# ha-pc-switch-revA.net
KiCad netlist of a schematic drawn in EAGLE
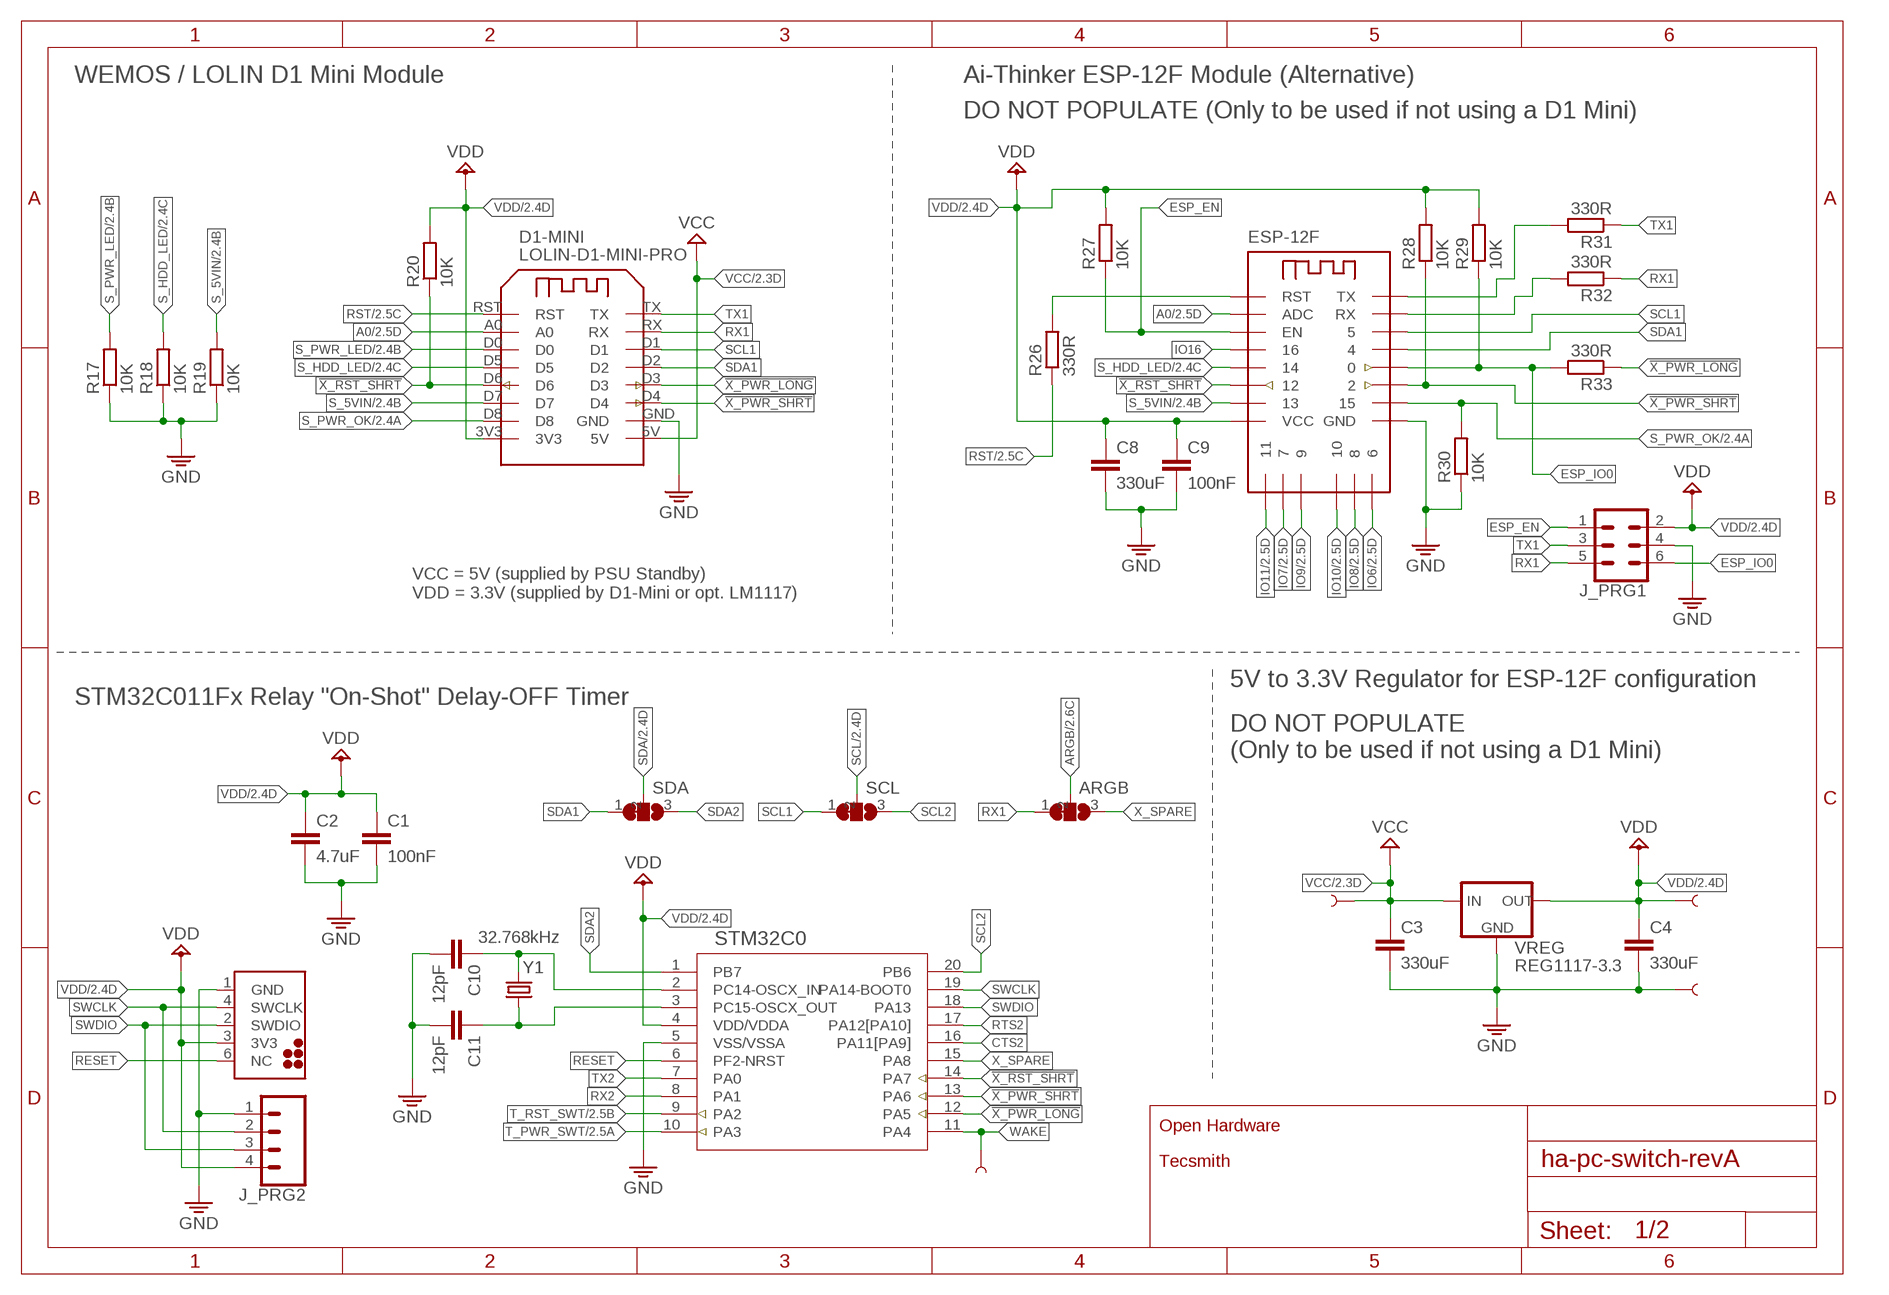
[diagram p0: schematic, sheet 1]
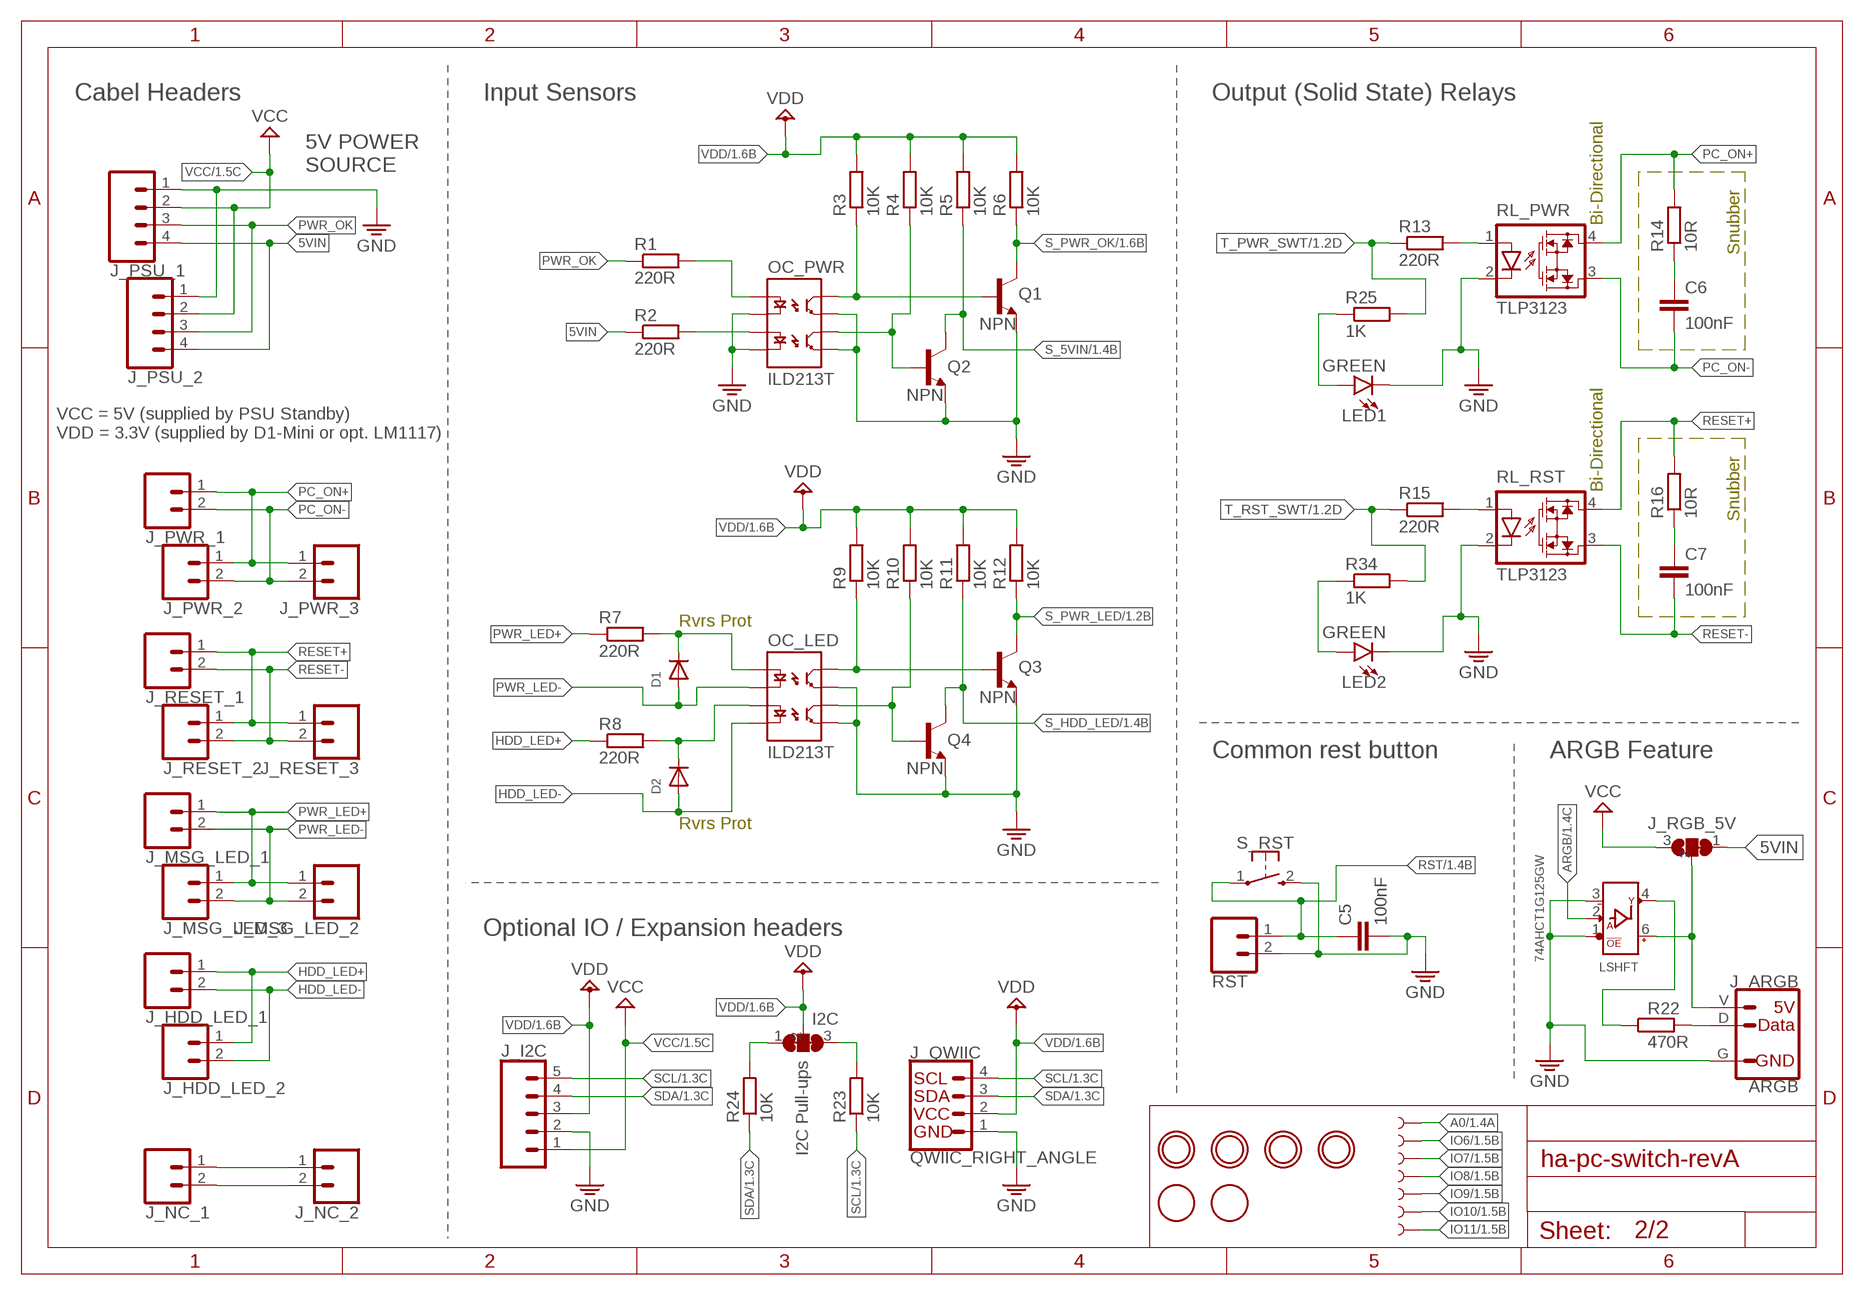
[diagram p1: schematic, sheet 2]

(export (version "E")
  (design (tool "Eeschema 10.0.6"))
  (components
    (comp (ref "ARGB")
      (value "JUMPER-1X3-CLOSED")
      (footprint "eagle-import:SOLDERJUMPER_CLOSEDWIRE-3")
      (libsource (lib "eagle-import") (part "JUMPER-1X3-CLOSED"))
    )
    (comp (ref "C1")
      (value "100nF")
      (footprint "eagle-import:C0603")
      (libsource (lib "eagle-import") (part "C-EUC0603"))
    )
    (comp (ref "C2")
      (value "4.7uF")
      (footprint "eagle-import:C0603")
      (libsource (lib "eagle-import") (part "C-EUC0603"))
    )
    (comp (ref "C3")
      (value "330uF")
      (footprint "eagle-import:C0603")
      (libsource (lib "eagle-import") (part "C-EUC0603"))
    )
    (comp (ref "C4")
      (value "330uF")
      (footprint "eagle-import:C0603")
      (libsource (lib "eagle-import") (part "C-EUC0603"))
    )
    (comp (ref "C8")
      (value "330uF")
      (footprint "eagle-import:C0603")
      (libsource (lib "eagle-import") (part "C-EUC0603"))
    )
    (comp (ref "C9")
      (value "100nF")
      (footprint "eagle-import:C0603")
      (libsource (lib "eagle-import") (part "C-EUC0603"))
    )
    (comp (ref "C10")
      (value "12pF")
      (footprint "eagle-import:C0603")
      (libsource (lib "eagle-import") (part "C-EUC0603"))
    )
    (comp (ref "C11")
      (value "12pF")
      (footprint "eagle-import:C0603")
      (libsource (lib "eagle-import") (part "C-EUC0603"))
    )
    (comp (ref "D1-MINI")
      (value "LOLIN-D1-MINI-PRO")
      (footprint "eagle-import:WEMOS-D1-MINI-PRO")
      (libsource (lib "eagle-import") (part "LOLIN-D1-MINI-PRO"))
    )
    (comp (ref "ESP-12F")
      (value "ESPRESSIF-ESP-12F&ESMD")
      (footprint "eagle-import:ESP8266-ESP-12E")
      (libsource (lib "eagle-import") (part "ESPRESSIF-ESP-12F&ESMD"))
    )
    (comp (ref "J_DBG2")
      (value "NUCLEO_HEADER")
      (footprint "eagle-import:NUCLEO")
      (libsource (lib "eagle-import") (part "NUCLEO_HEADER"))
    )
    (comp (ref "J_PRG1")
      (value "CONN_03X2FEMALE_SMD")
      (footprint "eagle-import:2X3_SMD")
      (libsource (lib "eagle-import") (part "CONN_03X2FEMALE_SMD"))
    )
    (comp (ref "J_PRG2")
      (value "1X04_SMD_STRAIGHT_COMBO")
      (footprint "eagle-import:1X04_SMD_VERTICAL_COMBO")
      (libsource (lib "eagle-import") (part "CONN_04SMD_STRAIGHT_COMBO"))
    )
    (comp (ref "LOGO1")
      (value "OSHW-LOGOM")
      (footprint "eagle-import:OSHW-LOGO-M")
      (libsource (lib "eagle-import") (part "OSHW-LOGOM"))
    )
    (comp (ref "R17")
      (value "10K")
      (footprint "eagle-import:R0603")
      (libsource (lib "eagle-import") (part "R-EU_R0603"))
    )
    (comp (ref "R18")
      (value "10K")
      (footprint "eagle-import:R0603")
      (libsource (lib "eagle-import") (part "R-EU_R0603"))
    )
    (comp (ref "R19")
      (value "10K")
      (footprint "eagle-import:R0603")
      (libsource (lib "eagle-import") (part "R-EU_R0603"))
    )
    (comp (ref "R20")
      (value "10K")
      (footprint "eagle-import:R0603")
      (libsource (lib "eagle-import") (part "R-EU_R0603"))
    )
    (comp (ref "R26")
      (value "330R")
      (footprint "eagle-import:R0603")
      (libsource (lib "eagle-import") (part "R-EU_R0603"))
    )
    (comp (ref "R27")
      (value "10K")
      (footprint "eagle-import:R0603")
      (libsource (lib "eagle-import") (part "R-EU_R0603"))
    )
    (comp (ref "R28")
      (value "10K")
      (footprint "eagle-import:R0603")
      (libsource (lib "eagle-import") (part "R-EU_R0603"))
    )
    (comp (ref "R29")
      (value "10K")
      (footprint "eagle-import:R0603")
      (libsource (lib "eagle-import") (part "R-EU_R0603"))
    )
    (comp (ref "R30")
      (value "10K")
      (footprint "eagle-import:R0603")
      (libsource (lib "eagle-import") (part "R-EU_R0603"))
    )
    (comp (ref "R31")
      (value "330R")
      (footprint "eagle-import:R0603")
      (libsource (lib "eagle-import") (part "R-EU_R0603"))
    )
    (comp (ref "R32")
      (value "330R")
      (footprint "eagle-import:R0603")
      (libsource (lib "eagle-import") (part "R-EU_R0603"))
    )
    (comp (ref "R33")
      (value "330R")
      (footprint "eagle-import:R0603")
      (libsource (lib "eagle-import") (part "R-EU_R0603"))
    )
    (comp (ref "SCL")
      (value "JUMPER-1X3-CLOSED")
      (footprint "eagle-import:SOLDERJUMPER_CLOSEDWIRE-3")
      (libsource (lib "eagle-import") (part "JUMPER-1X3-CLOSED"))
    )
    (comp (ref "SDA")
      (value "JUMPER-1X3-CLOSED")
      (footprint "eagle-import:SOLDERJUMPER_CLOSEDWIRE-3")
      (libsource (lib "eagle-import") (part "JUMPER-1X3-CLOSED"))
    )
    (comp (ref "STM32C0")
      (value "STM32C011FTSSOP20_STM-M")
      (footprint "eagle-import:TSSOP20-M")
      (fields
        (field (name "MANUFACTURER_PART_NUMBER") "STM32C011F4P6")
        (field (name "COPYRIGHT") "Copyright (C) 2024 Ultra Librarian. All rights reserved.")
      )
      (libsource (lib "eagle-import") (part "STM32C011FTSSOP20_STM-M"))
    )
    (comp (ref "TP1")
      (value "TEST-POINT3X5")
      (footprint "eagle-import:PAD.03X.05")
      (libsource (lib "eagle-import") (part "TEST-POINT3X5"))
    )
    (comp (ref "TP2")
      (value "TEST-POINT3X5")
      (footprint "eagle-import:PAD.03X.05")
      (libsource (lib "eagle-import") (part "TEST-POINT3X5"))
    )
    (comp (ref "TP3")
      (value "TEST-POINT3X5")
      (footprint "eagle-import:PAD.03X.05")
      (libsource (lib "eagle-import") (part "TEST-POINT3X5"))
    )
    (comp (ref "TP4")
      (value "TEST-POINT3X5")
      (footprint "eagle-import:PAD.03X.05")
      (libsource (lib "eagle-import") (part "TEST-POINT3X5"))
    )
    (comp (ref "U$1")
      (value "TECSMITH-LOGOLONG")
      (footprint "eagle-import:TECSMITH-NAME")
      (libsource (lib "eagle-import") (part "TECSMITH-LOGOLONG"))
    )
    (comp (ref "VREG")
      (value "REG1117-3.3")
      (footprint "eagle-import:SOT223")
      (libsource (lib "eagle-import") (part "REG1117-3.3"))
    )
    (comp (ref "Y1")
      (value "32.768kHz")
      (footprint "eagle-import:CRYSTAL-SMD-3.2X1.5MM")
      (libsource (lib "eagle-import") (part "CRYSTAL-32.768KHZSMD-3.2X1.5"))
    )
    (comp (ref "C5")
      (value "100nF")
      (footprint "eagle-import:C0603")
      (libsource (lib "eagle-import") (part "C-EUC0603"))
    )
    (comp (ref "C6")
      (value "100nF")
      (footprint "eagle-import:C0603")
      (libsource (lib "eagle-import") (part "C-EUC0603"))
    )
    (comp (ref "C7")
      (value "100nF")
      (footprint "eagle-import:C0603")
      (libsource (lib "eagle-import") (part "C-EUC0603"))
    )
    (comp (ref "D1")
      (value "DIODESOD-523")
      (footprint "eagle-import:SOD-523")
      (libsource (lib "eagle-import") (part "DIODESOD-523"))
    )
    (comp (ref "D2")
      (value "DIODESOD-523")
      (footprint "eagle-import:SOD-523")
      (libsource (lib "eagle-import") (part "DIODESOD-523"))
    )
    (comp (ref "I2C")
      (value "JUMPER-1X3-CLOSED-2")
      (footprint "eagle-import:SOLDERJUMPER_CLOSEDWIRE-3-2")
      (libsource (lib "eagle-import") (part "JUMPER-1X3-CLOSED-2"))
    )
    (comp (ref "J_ARGB")
      (value "ARGB")
      (footprint "eagle-import:ARGB")
      (libsource (lib "eagle-import") (part "ARGB"))
    )
    (comp (ref "J_HDD_LED_1")
      (value "CONN_021X02_NO_SILK")
      (footprint "eagle-import:1X02_NO_SILK")
      (libsource (lib "eagle-import") (part "CONN_021X02_NO_SILK"))
    )
    (comp (ref "J_HDD_LED_2")
      (value "CONN_021X02_NO_SILK")
      (footprint "eagle-import:1X02_NO_SILK")
      (libsource (lib "eagle-import") (part "CONN_021X02_NO_SILK"))
    )
    (comp (ref "J_I2C")
      (value "CONN_05SCREW")
      (footprint "eagle-import:SCREWTERMINAL-3.5MM-5")
      (libsource (lib "eagle-import") (part "CONN_05SCREW"))
    )
    (comp (ref "J_MSG_LED_1")
      (value "CONN_021X02_NO_SILK")
      (footprint "eagle-import:1X02_NO_SILK")
      (libsource (lib "eagle-import") (part "CONN_021X02_NO_SILK"))
    )
    (comp (ref "J_MSG_LED_2")
      (value "CONN_021X02_NO_SILK")
      (footprint "eagle-import:1X02_NO_SILK")
      (libsource (lib "eagle-import") (part "CONN_021X02_NO_SILK"))
    )
    (comp (ref "J_MSG_LED_3")
      (value "CONN_02PTH3")
      (footprint "eagle-import:1X02_LONGPADS")
      (libsource (lib "eagle-import") (part "CONN_02PTH3"))
    )
    (comp (ref "J_NC_1")
      (value "CONN_021X02_NO_SILK")
      (footprint "eagle-import:1X02_NO_SILK")
      (libsource (lib "eagle-import") (part "CONN_021X02_NO_SILK"))
    )
    (comp (ref "J_NC_2")
      (value "CONN_021X02_NO_SILK")
      (footprint "eagle-import:1X02_NO_SILK")
      (libsource (lib "eagle-import") (part "CONN_021X02_NO_SILK"))
    )
    (comp (ref "J_PSU_1")
      (value "CONN_04LONGPADS")
      (footprint "eagle-import:1X04_LONGPADS")
      (libsource (lib "eagle-import") (part "CONN_04LONGPADS"))
    )
    (comp (ref "J_PSU_2")
      (value "CONN_04SCREW")
      (footprint "eagle-import:SCREWTERMINAL-3.5MM-4")
      (libsource (lib "eagle-import") (part "CONN_04SCREW"))
    )
    (comp (ref "J_PWR_1")
      (value "CONN_021X02_NO_SILK")
      (footprint "eagle-import:1X02_NO_SILK")
      (libsource (lib "eagle-import") (part "CONN_021X02_NO_SILK"))
    )
    (comp (ref "J_PWR_2")
      (value "CONN_021X02_NO_SILK")
      (footprint "eagle-import:1X02_NO_SILK")
      (libsource (lib "eagle-import") (part "CONN_021X02_NO_SILK"))
    )
    (comp (ref "J_PWR_3")
      (value "CONN_02PTH3")
      (footprint "eagle-import:1X02_LONGPADS")
      (libsource (lib "eagle-import") (part "CONN_02PTH3"))
    )
    (comp (ref "J_QWIIC")
      (value "QWIIC_RIGHT_ANGLE")
      (footprint "eagle-import:JST04_1MM_RA")
      (libsource (lib "eagle-import") (part "QWIIC_CONNECTORJS-1MM"))
    )
    (comp (ref "J_RESET_1")
      (value "CONN_021X02_NO_SILK")
      (footprint "eagle-import:1X02_NO_SILK")
      (libsource (lib "eagle-import") (part "CONN_021X02_NO_SILK"))
    )
    (comp (ref "J_RESET_2")
      (value "CONN_021X02_NO_SILK")
      (footprint "eagle-import:1X02_NO_SILK")
      (libsource (lib "eagle-import") (part "CONN_021X02_NO_SILK"))
    )
    (comp (ref "J_RESET_3")
      (value "CONN_02PTH3")
      (footprint "eagle-import:1X02_LONGPADS")
      (libsource (lib "eagle-import") (part "CONN_02PTH3"))
    )
    (comp (ref "J_RGB_5V")
      (value "JUMPER-1X3-CLOSEDPINS")
      (footprint "eagle-import:1X03_ROUND_CLOSED")
      (libsource (lib "eagle-import") (part "JUMPER-1X3-CLOSEDPINS"))
    )
    (comp (ref "LED1")
      (value "GREEN")
      (footprint "eagle-import:LED-0603")
      (libsource (lib "eagle-import") (part "LED-GREEN0603"))
    )
    (comp (ref "LED2")
      (value "GREEN")
      (footprint "eagle-import:LED-0603")
      (libsource (lib "eagle-import") (part "LED-GREEN0603"))
    )
    (comp (ref "LSHFT")
      (value "74AHCT1G125GW")
      (footprint "eagle-import:SC-88A__TSSOP5__SOT353-1")
      (libsource (lib "eagle-import") (part "74AHCT1G125GW"))
    )
    (comp (ref "OC_LED")
      (value "ILD213T")
      (footprint "eagle-import:SO08-2")
      (libsource (lib "eagle-import") (part "OPTOISOLATOR-2SOIC8"))
    )
    (comp (ref "OC_PWR")
      (value "ILD213T")
      (footprint "eagle-import:SO08-2")
      (libsource (lib "eagle-import") (part "OPTOISOLATOR-2SOIC8"))
    )
    (comp (ref "Q1")
      (value "NPN")
      (footprint "eagle-import:SOT23-3")
      (libsource (lib "eagle-import") (part "TRANSISTOR_NPNSOT23-3"))
    )
    (comp (ref "Q2")
      (value "NPN")
      (footprint "eagle-import:SOT23-3")
      (libsource (lib "eagle-import") (part "TRANSISTOR_NPNSOT23-3"))
    )
    (comp (ref "Q3")
      (value "NPN")
      (footprint "eagle-import:SOT23-3")
      (libsource (lib "eagle-import") (part "TRANSISTOR_NPNSOT23-3"))
    )
    (comp (ref "Q4")
      (value "NPN")
      (footprint "eagle-import:SOT23-3")
      (libsource (lib "eagle-import") (part "TRANSISTOR_NPNSOT23-3"))
    )
    (comp (ref "R1")
      (value "220R")
      (footprint "eagle-import:R0603")
      (libsource (lib "eagle-import") (part "R-EU_R0603"))
    )
    (comp (ref "R2")
      (value "220R")
      (footprint "eagle-import:R0603")
      (libsource (lib "eagle-import") (part "R-EU_R0603"))
    )
    (comp (ref "R3")
      (value "10K")
      (footprint "eagle-import:R0603")
      (libsource (lib "eagle-import") (part "R-EU_R0603"))
    )
    (comp (ref "R4")
      (value "10K")
      (footprint "eagle-import:R0603")
      (libsource (lib "eagle-import") (part "R-EU_R0603"))
    )
    (comp (ref "R5")
      (value "10K")
      (footprint "eagle-import:R0603")
      (libsource (lib "eagle-import") (part "R-EU_R0603"))
    )
    (comp (ref "R6")
      (value "10K")
      (footprint "eagle-import:R0603")
      (libsource (lib "eagle-import") (part "R-EU_R0603"))
    )
    (comp (ref "R7")
      (value "220R")
      (footprint "eagle-import:R0603")
      (libsource (lib "eagle-import") (part "R-EU_R0603"))
    )
    (comp (ref "R8")
      (value "220R")
      (footprint "eagle-import:R0603")
      (libsource (lib "eagle-import") (part "R-EU_R0603"))
    )
    (comp (ref "R9")
      (value "10K")
      (footprint "eagle-import:R0603")
      (libsource (lib "eagle-import") (part "R-EU_R0603"))
    )
    (comp (ref "R10")
      (value "10K")
      (footprint "eagle-import:R0603")
      (libsource (lib "eagle-import") (part "R-EU_R0603"))
    )
    (comp (ref "R11")
      (value "10K")
      (footprint "eagle-import:R0603")
      (libsource (lib "eagle-import") (part "R-EU_R0603"))
    )
    (comp (ref "R12")
      (value "10K")
      (footprint "eagle-import:R0603")
      (libsource (lib "eagle-import") (part "R-EU_R0603"))
    )
    (comp (ref "R13")
      (value "220R")
      (footprint "eagle-import:R0603")
      (libsource (lib "eagle-import") (part "R-EU_R0603"))
    )
    (comp (ref "R14")
      (value "10R")
      (footprint "eagle-import:R0603")
      (libsource (lib "eagle-import") (part "R-EU_R0603"))
    )
    (comp (ref "R15")
      (value "220R")
      (footprint "eagle-import:R0603")
      (libsource (lib "eagle-import") (part "R-EU_R0603"))
    )
    (comp (ref "R16")
      (value "10R")
      (footprint "eagle-import:R0603")
      (libsource (lib "eagle-import") (part "R-EU_R0603"))
    )
    (comp (ref "R22")
      (value "470R")
      (footprint "eagle-import:R0603")
      (libsource (lib "eagle-import") (part "R-EU_R0603"))
    )
    (comp (ref "R23")
      (value "10K")
      (footprint "eagle-import:R0603")
      (libsource (lib "eagle-import") (part "R-EU_R0603"))
    )
    (comp (ref "R24")
      (value "10K")
      (footprint "eagle-import:R0603")
      (libsource (lib "eagle-import") (part "R-EU_R0603"))
    )
    (comp (ref "R25")
      (value "1K")
      (footprint "eagle-import:R0603")
      (libsource (lib "eagle-import") (part "R-EU_R0603"))
    )
    (comp (ref "R34")
      (value "1K")
      (footprint "eagle-import:R0603")
      (libsource (lib "eagle-import") (part "R-EU_R0603"))
    )
    (comp (ref "RL_PWR")
      (value "TLP3123")
      (footprint "eagle-import:SOP4_TOS")
      (libsource (lib "eagle-import") (part "TLP3123"))
    )
    (comp (ref "RL_RST")
      (value "TLP3123")
      (footprint "eagle-import:SOP4_TOS")
      (libsource (lib "eagle-import") (part "TLP3123"))
    )
    (comp (ref "RST")
      (value "CONN_021X02_NO_SILK")
      (footprint "eagle-import:1X02_NO_SILK")
      (libsource (lib "eagle-import") (part "CONN_021X02_NO_SILK"))
    )
    (comp (ref "S_RST")
      (value "MOMENTARY-SWITCH-SPST-1")
      (footprint "eagle-import:SKRKAEE020")
      (libsource (lib "eagle-import") (part "MOMENTARY-SWITCH-SPST-1"))
    )
    (comp (ref "TP9")
      (value "TEST-POINT3X5")
      (footprint "eagle-import:PAD.03X.05")
      (libsource (lib "eagle-import") (part "TEST-POINT3X5"))
    )
    (comp (ref "TP10")
      (value "TEST-POINT3X5")
      (footprint "eagle-import:PAD.03X.05")
      (libsource (lib "eagle-import") (part "TEST-POINT3X5"))
    )
    (comp (ref "TP11")
      (value "TEST-POINT3X5")
      (footprint "eagle-import:PAD.03X.05")
      (libsource (lib "eagle-import") (part "TEST-POINT3X5"))
    )
    (comp (ref "TP12")
      (value "TEST-POINT3X5")
      (footprint "eagle-import:PAD.03X.05")
      (libsource (lib "eagle-import") (part "TEST-POINT3X5"))
    )
    (comp (ref "TP14")
      (value "TEST-POINT3X5")
      (footprint "eagle-import:PAD.03X.05")
      (libsource (lib "eagle-import") (part "TEST-POINT3X5"))
    )
    (comp (ref "TP15")
      (value "TEST-POINT3X5")
      (footprint "eagle-import:PAD.03X.05")
      (libsource (lib "eagle-import") (part "TEST-POINT3X5"))
    )
    (comp (ref "TP16")
      (value "TEST-POINT3X5")
      (footprint "eagle-import:PAD.03X.05")
      (libsource (lib "eagle-import") (part "TEST-POINT3X5"))
    )
    (comp (ref "U$5")
      (value "MOUNTINGHOLE3.0THIN")
      (footprint "eagle-import:MOUNTINGHOLE_3.0_PLATEDTHIN")
      (libsource (lib "eagle-import") (part "MOUNTINGHOLE3.0THIN"))
    )
    (comp (ref "U$9")
      (value "MOUNTINGHOLE3.0THIN")
      (footprint "eagle-import:MOUNTINGHOLE_3.0_PLATEDTHIN")
      (libsource (lib "eagle-import") (part "MOUNTINGHOLE3.0THIN"))
    )
    (comp (ref "U$11")
      (value "MOUNTINGHOLE3.0THIN")
      (footprint "eagle-import:MOUNTINGHOLE_3.0_PLATEDTHIN")
      (libsource (lib "eagle-import") (part "MOUNTINGHOLE3.0THIN"))
    )
    (comp (ref "U$12")
      (value "MOUNTINGHOLE3.0THIN")
      (footprint "eagle-import:MOUNTINGHOLE_3.0_PLATEDTHIN")
      (libsource (lib "eagle-import") (part "MOUNTINGHOLE3.0THIN"))
    )
    (comp (ref "U$15")
      (value "FIDUCIAL")
      (footprint "eagle-import:FIDUCIAL_1MM")
      (libsource (lib "eagle-import") (part "FIDUCIAL"))
    )
    (comp (ref "U$16")
      (value "FIDUCIAL")
      (footprint "eagle-import:FIDUCIAL_1MM")
      (libsource (lib "eagle-import") (part "FIDUCIAL"))
    )
  )
  (nets
    (net (code "1") (name "5VIN") (class "Default")
      (node (ref "J_PSU_1") (pin "4") (pinfunction "4_4") (pintype "passive"))
      (node (ref "J_PSU_2") (pin "4") (pinfunction "4_4") (pintype "passive"))
      (node (ref "J_RGB_5V") (pin "1") (pinfunction "1_1") (pintype "passive"))
      (node (ref "R2") (pin "1") (pinfunction "1_1") (pintype "passive"))
    )
    (net (code "2") (name "A0") (class "Default")
      (node (ref "D1-MINI") (pin "A0") (pinfunction "A0_A0") (pintype "bidirectional"))
      (node (ref "ESP-12F") (pin "ADC0") (pinfunction "ADC_ADC0") (pintype "bidirectional"))
      (node (ref "TP12") (pin "1") (pinfunction "1_1") (pintype "bidirectional"))
    )
    (net (code "3") (name "ARGB") (class "Default")
      (node (ref "ARGB") (pin "2") (pinfunction "2_2") (pintype "passive"))
      (node (ref "LSHFT") (pin "2") (pinfunction "A_DIN_2") (pintype "input"))
    )
    (net (code "4") (name "CTS2") (class "Default")
      (node (ref "STM32C0") (pin "16") (pinfunction "PA11[PA9]_16") (pintype "bidirectional"))
    )
    (net (code "5") (name "ESP_EN") (class "Default")
      (node (ref "ESP-12F") (pin "EN") (pinfunction "EN_EN") (pintype "bidirectional"))
      (node (ref "J_PRG1") (pin "1") (pinfunction "1_1") (pintype "bidirectional"))
      (node (ref "R27") (pin "1") (pinfunction "1_1") (pintype "passive"))
    )
    (net (code "6") (name "ESP_IO0") (class "Default")
      (node (ref "ESP-12F") (pin "GPIO0") (pinfunction "0_GPIO0") (pintype "bidirectional"))
      (node (ref "J_PRG1") (pin "6") (pinfunction "6_6") (pintype "bidirectional"))
      (node (ref "R29") (pin "1") (pinfunction "1_1") (pintype "passive"))
      (node (ref "R33") (pin "2") (pinfunction "2_2") (pintype "passive"))
    )
    (net (code "7") (name "GND") (class "Default")
      (node (ref "C1") (pin "2") (pinfunction "2_2") (pintype "passive"))
      (node (ref "C10") (pin "2") (pinfunction "2_2") (pintype "passive"))
      (node (ref "C11") (pin "2") (pinfunction "2_2") (pintype "passive"))
      (node (ref "C2") (pin "2") (pinfunction "2_2") (pintype "passive"))
      (node (ref "C3") (pin "2") (pinfunction "2_2") (pintype "passive"))
      (node (ref "C4") (pin "2") (pinfunction "2_2") (pintype "passive"))
      (node (ref "C5") (pin "2") (pinfunction "2_2") (pintype "passive"))
      (node (ref "C8") (pin "2") (pinfunction "2_2") (pintype "passive"))
      (node (ref "C9") (pin "2") (pinfunction "2_2") (pintype "passive"))
      (node (ref "D1-MINI") (pin "GND") (pinfunction "GND_GND") (pintype "power_in"))
      (node (ref "ESP-12F") (pin "GND") (pinfunction "GND_GND") (pintype "bidirectional"))
      (node (ref "J_ARGB") (pin "G") (pinfunction "G_G") (pintype "power_in"))
      (node (ref "J_DBG2") (pin "1") (pinfunction "GND_1") (pintype "power_in"))
      (node (ref "J_I2C") (pin "2") (pinfunction "2_2") (pintype "passive"))
      (node (ref "J_PRG1") (pin "4") (pinfunction "4_4") (pintype "bidirectional"))
      (node (ref "J_PRG2") (pin "1") (pinfunction "1_1") (pintype "passive"))
      (node (ref "J_PSU_1") (pin "1") (pinfunction "1_1") (pintype "passive"))
      (node (ref "J_PSU_2") (pin "1") (pinfunction "1_1") (pintype "passive"))
      (node (ref "J_QWIIC") (pin "1") (pinfunction "1_1") (pintype "power_in"))
      (node (ref "LED1") (pin "C") (pinfunction "C_C") (pintype "passive"))
      (node (ref "LED2") (pin "C") (pinfunction "C_C") (pintype "passive"))
      (node (ref "LSHFT") (pin "1") (pinfunction "~{OE}_1") (pintype "input"))
      (node (ref "LSHFT") (pin "3") (pinfunction "3_GND_3") (pintype "power_in"))
      (node (ref "OC_LED") (pin "5") (pinfunction "EM2_5") (pintype "bidirectional"))
      (node (ref "OC_LED") (pin "7") (pinfunction "EM1_7") (pintype "bidirectional"))
      (node (ref "OC_PWR") (pin "2") (pinfunction "C1_2") (pintype "bidirectional"))
      (node (ref "OC_PWR") (pin "4") (pinfunction "C2_4") (pintype "bidirectional"))
      (node (ref "OC_PWR") (pin "5") (pinfunction "EM2_5") (pintype "bidirectional"))
      (node (ref "OC_PWR") (pin "7") (pinfunction "EM1_7") (pintype "bidirectional"))
      (node (ref "Q1") (pin "2") (pinfunction "E_2") (pintype "passive"))
      (node (ref "Q2") (pin "2") (pinfunction "E_2") (pintype "passive"))
      (node (ref "Q3") (pin "2") (pinfunction "E_2") (pintype "passive"))
      (node (ref "Q4") (pin "2") (pinfunction "E_2") (pintype "passive"))
      (node (ref "R17") (pin "1") (pinfunction "1_1") (pintype "passive"))
      (node (ref "R18") (pin "1") (pinfunction "1_1") (pintype "passive"))
      (node (ref "R19") (pin "1") (pinfunction "1_1") (pintype "passive"))
      (node (ref "R30") (pin "1") (pinfunction "1_1") (pintype "passive"))
      (node (ref "RL_PWR") (pin "2") (pinfunction "C_2") (pintype "passive"))
      (node (ref "RL_RST") (pin "2") (pinfunction "C_2") (pintype "passive"))
      (node (ref "RST") (pin "2") (pinfunction "2_2") (pintype "passive"))
      (node (ref "STM32C0") (pin "5") (pinfunction "VSS/VSSA_5") (pintype "power_in"))
      (node (ref "S_RST") (pin "2") (pinfunction "3_2") (pintype "passive"))
      (node (ref "TP3") (pin "1") (pinfunction "1_1") (pintype "bidirectional"))
      (node (ref "VREG") (pin "1") (pinfunction "GND_1") (pintype "power_in"))
    )
    (net (code "8") (name "HDD_LED+") (class "Default")
      (node (ref "J_HDD_LED_1") (pin "1") (pinfunction "1_1") (pintype "passive"))
      (node (ref "J_HDD_LED_2") (pin "1") (pinfunction "1_1") (pintype "passive"))
      (node (ref "R8") (pin "1") (pinfunction "1_1") (pintype "passive"))
    )
    (net (code "9") (name "HDD_LED-") (class "Default")
      (node (ref "D2") (pin "A") (pinfunction "A_A") (pintype "passive"))
      (node (ref "J_HDD_LED_1") (pin "2") (pinfunction "2_2") (pintype "passive"))
      (node (ref "J_HDD_LED_2") (pin "2") (pinfunction "2_2") (pintype "passive"))
      (node (ref "OC_LED") (pin "4") (pinfunction "C2_4") (pintype "bidirectional"))
    )
    (net (code "10") (name "IO6") (class "Default")
      (node (ref "ESP-12F") (pin "SCLK") (pinfunction "6_SCLK") (pintype "bidirectional"))
      (node (ref "TP11") (pin "1") (pinfunction "1_1") (pintype "bidirectional"))
    )
    (net (code "11") (name "IO7") (class "Default")
      (node (ref "ESP-12F") (pin "MISO") (pinfunction "7_MISO") (pintype "bidirectional"))
      (node (ref "TP10") (pin "1") (pinfunction "1_1") (pintype "bidirectional"))
    )
    (net (code "12") (name "IO8") (class "Default")
      (node (ref "ESP-12F") (pin "MOSI") (pinfunction "8_MOSI") (pintype "bidirectional"))
      (node (ref "TP9") (pin "1") (pinfunction "1_1") (pintype "bidirectional"))
    )
    (net (code "13") (name "IO9") (class "Default")
      (node (ref "ESP-12F") (pin "GPIO9") (pinfunction "9_GPIO9") (pintype "bidirectional"))
      (node (ref "TP16") (pin "1") (pinfunction "1_1") (pintype "bidirectional"))
    )
    (net (code "14") (name "IO10") (class "Default")
      (node (ref "ESP-12F") (pin "GPIO10") (pinfunction "10_GPIO10") (pintype "bidirectional"))
      (node (ref "TP15") (pin "1") (pinfunction "1_1") (pintype "bidirectional"))
    )
    (net (code "15") (name "IO11") (class "Default")
      (node (ref "ESP-12F") (pin "CS0") (pinfunction "11_CS0") (pintype "bidirectional"))
      (node (ref "TP14") (pin "1") (pinfunction "1_1") (pintype "bidirectional"))
    )
    (net (code "16") (name "IO16") (class "Default")
      (node (ref "ESP-12F") (pin "GPIO16") (pinfunction "16_GPIO16") (pintype "bidirectional"))
    )
    (net (code "17") (name "Net-(C6-Pad1)") (class "Default")
      (node (ref "C6") (pin "1") (pinfunction "1_1") (pintype "passive"))
      (node (ref "R14") (pin "1") (pinfunction "1_1") (pintype "passive"))
    )
    (net (code "18") (name "Net-(C7-Pad1)") (class "Default")
      (node (ref "C7") (pin "1") (pinfunction "1_1") (pintype "passive"))
      (node (ref "R16") (pin "1") (pinfunction "1_1") (pintype "passive"))
    )
    (net (code "19") (name "Net-(D1-C)") (class "Default")
      (node (ref "D1") (pin "K") (pinfunction "C_K") (pintype "passive"))
      (node (ref "OC_LED") (pin "1") (pinfunction "A1_1") (pintype "bidirectional"))
      (node (ref "R7") (pin "2") (pinfunction "2_2") (pintype "passive"))
    )
    (net (code "20") (name "Net-(D2-C)") (class "Default")
      (node (ref "D2") (pin "K") (pinfunction "C_K") (pintype "passive"))
      (node (ref "OC_LED") (pin "3") (pinfunction "A2_3") (pintype "bidirectional"))
      (node (ref "R8") (pin "2") (pinfunction "2_2") (pintype "passive"))
    )
    (net (code "21") (name "Net-(ESP-12F-PadRST)") (class "Default")
      (node (ref "ESP-12F") (pin "RST") (pinfunction "RST_RST") (pintype "bidirectional"))
      (node (ref "R26") (pin "2") (pinfunction "2_2") (pintype "passive"))
    )
    (net (code "22") (name "Net-(ESP-12F-RX)") (class "Default")
      (node (ref "ESP-12F") (pin "RXD0") (pinfunction "RX_RXD0") (pintype "bidirectional"))
      (node (ref "R32") (pin "2") (pinfunction "2_2") (pintype "passive"))
    )
    (net (code "23") (name "Net-(ESP-12F-TX)") (class "Default")
      (node (ref "ESP-12F") (pin "TXD0") (pinfunction "TX_TXD0") (pintype "bidirectional"))
      (node (ref "R31") (pin "2") (pinfunction "2_2") (pintype "passive"))
    )
    (net (code "24") (name "Net-(I2C-Pad1)") (class "Default")
      (node (ref "I2C") (pin "1") (pinfunction "1_1") (pintype "passive"))
      (node (ref "R24") (pin "2") (pinfunction "2_2") (pintype "passive"))
    )
    (net (code "25") (name "Net-(I2C-Pad3)") (class "Default")
      (node (ref "I2C") (pin "3") (pinfunction "3_3") (pintype "passive"))
      (node (ref "R23") (pin "2") (pinfunction "2_2") (pintype "passive"))
    )
    (net (code "26") (name "Net-(J_ARGB-PadD)") (class "Default")
      (node (ref "J_ARGB") (pin "D") (pinfunction "D_D") (pintype "passive"))
      (node (ref "R22") (pin "2") (pinfunction "2_2") (pintype "passive"))
    )
    (net (code "27") (name "Net-(J_NC_1-Pad1)") (class "Default")
      (node (ref "J_NC_1") (pin "1") (pinfunction "1_1") (pintype "passive"))
      (node (ref "J_NC_2") (pin "1") (pinfunction "1_1") (pintype "passive"))
    )
    (net (code "28") (name "Net-(J_NC_1-Pad2)") (class "Default")
      (node (ref "J_NC_1") (pin "2") (pinfunction "2_2") (pintype "passive"))
      (node (ref "J_NC_2") (pin "2") (pinfunction "2_2") (pintype "passive"))
    )
    (net (code "29") (name "Net-(LED1-PadA)") (class "Default")
      (node (ref "LED1") (pin "A") (pinfunction "A_A") (pintype "passive"))
      (node (ref "R25") (pin "1") (pinfunction "1_1") (pintype "passive"))
    )
    (net (code "30") (name "Net-(LED2-PadA)") (class "Default")
      (node (ref "LED2") (pin "A") (pinfunction "A_A") (pintype "passive"))
      (node (ref "R34") (pin "1") (pinfunction "1_1") (pintype "passive"))
    )
    (net (code "31") (name "Net-(LSHFT-5_VCC)") (class "Default")
      (node (ref "J_ARGB") (pin "V") (pinfunction "V_V") (pintype "power_in"))
      (node (ref "J_RGB_5V") (pin "2") (pinfunction "2_2") (pintype "passive"))
      (node (ref "LSHFT") (pin "6") (pinfunction "5_VCC_6") (pintype "power_in"))
    )
    (net (code "32") (name "Net-(LSHFT-Y_DOUT)") (class "Default")
      (node (ref "LSHFT") (pin "4") (pinfunction "Y_DOUT_4") (pintype "output"))
      (node (ref "R22") (pin "1") (pinfunction "1_1") (pintype "passive"))
    )
    (net (code "33") (name "Net-(OC_LED-CL1)") (class "Default")
      (node (ref "OC_LED") (pin "8") (pinfunction "CL1_8") (pintype "bidirectional"))
      (node (ref "Q3") (pin "1") (pinfunction "B_1") (pintype "passive"))
      (node (ref "R9") (pin "1") (pinfunction "1_1") (pintype "passive"))
    )
    (net (code "34") (name "Net-(OC_LED-CL2)") (class "Default")
      (node (ref "OC_LED") (pin "6") (pinfunction "CL2_6") (pintype "bidirectional"))
      (node (ref "Q4") (pin "1") (pinfunction "B_1") (pintype "passive"))
      (node (ref "R10") (pin "1") (pinfunction "1_1") (pintype "passive"))
    )
    (net (code "35") (name "Net-(OC_PWR-A1)") (class "Default")
      (node (ref "OC_PWR") (pin "1") (pinfunction "A1_1") (pintype "bidirectional"))
      (node (ref "R1") (pin "2") (pinfunction "2_2") (pintype "passive"))
    )
    (net (code "36") (name "Net-(OC_PWR-A2)") (class "Default")
      (node (ref "OC_PWR") (pin "3") (pinfunction "A2_3") (pintype "bidirectional"))
      (node (ref "R2") (pin "2") (pinfunction "2_2") (pintype "passive"))
    )
    (net (code "37") (name "Net-(OC_PWR-CL1)") (class "Default")
      (node (ref "OC_PWR") (pin "8") (pinfunction "CL1_8") (pintype "bidirectional"))
      (node (ref "Q1") (pin "1") (pinfunction "B_1") (pintype "passive"))
      (node (ref "R3") (pin "1") (pinfunction "1_1") (pintype "passive"))
    )
    (net (code "38") (name "Net-(OC_PWR-CL2)") (class "Default")
      (node (ref "OC_PWR") (pin "6") (pinfunction "CL2_6") (pintype "bidirectional"))
      (node (ref "Q2") (pin "1") (pinfunction "B_1") (pintype "passive"))
      (node (ref "R4") (pin "1") (pinfunction "1_1") (pintype "passive"))
    )
    (net (code "39") (name "Net-(RL_PWR-A)") (class "Default")
      (node (ref "R13") (pin "2") (pinfunction "2_2") (pintype "passive"))
      (node (ref "RL_PWR") (pin "1") (pinfunction "A_1") (pintype "passive"))
    )
    (net (code "40") (name "Net-(RL_RST-A)") (class "Default")
      (node (ref "R15") (pin "2") (pinfunction "2_2") (pintype "passive"))
      (node (ref "RL_RST") (pin "1") (pinfunction "A_1") (pintype "passive"))
    )
    (net (code "41") (name "Net-(STM32C0-PC14-OSCX_IN)") (class "Default")
      (node (ref "C10") (pin "1") (pinfunction "1_1") (pintype "passive"))
      (node (ref "STM32C0") (pin "2") (pinfunction "PC14-OSCX_IN_2") (pintype "bidirectional"))
      (node (ref "Y1") (pin "P$2") (pinfunction "2_P$2") (pintype "passive"))
    )
    (net (code "42") (name "Net-(STM32C0-PC15-OSCX_OUT)") (class "Default")
      (node (ref "C11") (pin "1") (pinfunction "1_1") (pintype "passive"))
      (node (ref "STM32C0") (pin "3") (pinfunction "PC15-OSCX_OUT_3") (pintype "bidirectional"))
      (node (ref "Y1") (pin "P$1") (pinfunction "1_P$1") (pintype "passive"))
    )
    (net (code "43") (name "PC_ON+") (class "Default")
      (node (ref "J_PWR_1") (pin "1") (pinfunction "1_1") (pintype "passive"))
      (node (ref "J_PWR_2") (pin "1") (pinfunction "1_1") (pintype "passive"))
      (node (ref "J_PWR_3") (pin "1") (pinfunction "1_1") (pintype "passive"))
      (node (ref "R14") (pin "2") (pinfunction "2_2") (pintype "passive"))
      (node (ref "RL_PWR") (pin "4") (pinfunction "D1_4") (pintype "passive"))
    )
    (net (code "44") (name "PC_ON-") (class "Default")
      (node (ref "C6") (pin "2") (pinfunction "2_2") (pintype "passive"))
      (node (ref "J_PWR_1") (pin "2") (pinfunction "2_2") (pintype "passive"))
      (node (ref "J_PWR_2") (pin "2") (pinfunction "2_2") (pintype "passive"))
      (node (ref "J_PWR_3") (pin "2") (pinfunction "2_2") (pintype "passive"))
      (node (ref "RL_PWR") (pin "3") (pinfunction "D2_3") (pintype "passive"))
    )
    (net (code "45") (name "PWR_LED+") (class "Default")
      (node (ref "J_MSG_LED_1") (pin "1") (pinfunction "1_1") (pintype "passive"))
      (node (ref "J_MSG_LED_2") (pin "1") (pinfunction "1_1") (pintype "passive"))
      (node (ref "J_MSG_LED_3") (pin "1") (pinfunction "1_1") (pintype "passive"))
      (node (ref "R7") (pin "1") (pinfunction "1_1") (pintype "passive"))
    )
    (net (code "46") (name "PWR_LED-") (class "Default")
      (node (ref "D1") (pin "A") (pinfunction "A_A") (pintype "passive"))
      (node (ref "J_MSG_LED_1") (pin "2") (pinfunction "2_2") (pintype "passive"))
      (node (ref "J_MSG_LED_2") (pin "2") (pinfunction "2_2") (pintype "passive"))
      (node (ref "J_MSG_LED_3") (pin "2") (pinfunction "2_2") (pintype "passive"))
      (node (ref "OC_LED") (pin "2") (pinfunction "C1_2") (pintype "bidirectional"))
    )
    (net (code "47") (name "PWR_OK") (class "Default")
      (node (ref "J_PSU_1") (pin "3") (pinfunction "3_3") (pintype "passive"))
      (node (ref "J_PSU_2") (pin "3") (pinfunction "3_3") (pintype "passive"))
      (node (ref "R1") (pin "1") (pinfunction "1_1") (pintype "passive"))
    )
    (net (code "48") (name "RESET") (class "Default")
      (node (ref "J_DBG2") (pin "6") (pinfunction "NC_6") (pintype "passive"))
      (node (ref "STM32C0") (pin "6") (pinfunction "PF2-NRST_6") (pintype "bidirectional"))
    )
    (net (code "49") (name "RESET+") (class "Default")
      (node (ref "J_RESET_1") (pin "1") (pinfunction "1_1") (pintype "passive"))
      (node (ref "J_RESET_2") (pin "1") (pinfunction "1_1") (pintype "passive"))
      (node (ref "J_RESET_3") (pin "1") (pinfunction "1_1") (pintype "passive"))
      (node (ref "R16") (pin "2") (pinfunction "2_2") (pintype "passive"))
      (node (ref "RL_RST") (pin "4") (pinfunction "D1_4") (pintype "passive"))
    )
    (net (code "50") (name "RESET-") (class "Default")
      (node (ref "C7") (pin "2") (pinfunction "2_2") (pintype "passive"))
      (node (ref "J_RESET_1") (pin "2") (pinfunction "2_2") (pintype "passive"))
      (node (ref "J_RESET_2") (pin "2") (pinfunction "2_2") (pintype "passive"))
      (node (ref "J_RESET_3") (pin "2") (pinfunction "2_2") (pintype "passive"))
      (node (ref "RL_RST") (pin "3") (pinfunction "D2_3") (pintype "passive"))
    )
    (net (code "51") (name "RST") (class "Default")
      (node (ref "C5") (pin "1") (pinfunction "1_1") (pintype "passive"))
      (node (ref "D1-MINI") (pin "RST") (pinfunction "RST_RST") (pintype "bidirectional"))
      (node (ref "R26") (pin "1") (pinfunction "1_1") (pintype "passive"))
      (node (ref "RST") (pin "1") (pinfunction "1_1") (pintype "passive"))
      (node (ref "S_RST") (pin "1") (pinfunction "1_1") (pintype "passive"))
    )
    (net (code "52") (name "RTS2") (class "Default")
      (node (ref "STM32C0") (pin "17") (pinfunction "PA12[PA10]_17") (pintype "bidirectional"))
    )
    (net (code "53") (name "RX1") (class "Default")
      (node (ref "ARGB") (pin "1") (pinfunction "1_1") (pintype "passive"))
      (node (ref "D1-MINI") (pin "RX") (pinfunction "RX_RX") (pintype "bidirectional"))
      (node (ref "J_PRG1") (pin "5") (pinfunction "5_5") (pintype "bidirectional"))
      (node (ref "R32") (pin "1") (pinfunction "1_1") (pintype "passive"))
    )
    (net (code "54") (name "RX2") (class "Default")
      (node (ref "STM32C0") (pin "8") (pinfunction "PA1_8") (pintype "bidirectional"))
    )
    (net (code "55") (name "SCL") (class "Default")
      (node (ref "J_I2C") (pin "5") (pinfunction "5_5") (pintype "passive"))
      (node (ref "J_QWIIC") (pin "4") (pinfunction "4_4") (pintype "passive"))
      (node (ref "R23") (pin "1") (pinfunction "1_1") (pintype "passive"))
      (node (ref "SCL") (pin "2") (pinfunction "2_2") (pintype "passive"))
    )
    (net (code "56") (name "SCL1") (class "Default")
      (node (ref "D1-MINI") (pin "D1") (pinfunction "D1_D1") (pintype "bidirectional"))
      (node (ref "ESP-12F") (pin "GPIO5") (pinfunction "5_GPIO5") (pintype "bidirectional"))
      (node (ref "SCL") (pin "1") (pinfunction "1_1") (pintype "passive"))
    )
    (net (code "57") (name "SCL2") (class "Default")
      (node (ref "SCL") (pin "3") (pinfunction "3_3") (pintype "passive"))
      (node (ref "STM32C0") (pin "20") (pinfunction "PB6_20") (pintype "bidirectional"))
    )
    (net (code "58") (name "SDA") (class "Default")
      (node (ref "J_I2C") (pin "4") (pinfunction "4_4") (pintype "passive"))
      (node (ref "J_QWIIC") (pin "3") (pinfunction "3_3") (pintype "passive"))
      (node (ref "R24") (pin "1") (pinfunction "1_1") (pintype "passive"))
      (node (ref "SDA") (pin "2") (pinfunction "2_2") (pintype "passive"))
    )
    (net (code "59") (name "SDA1") (class "Default")
      (node (ref "D1-MINI") (pin "D2") (pinfunction "D2_D2") (pintype "bidirectional"))
      (node (ref "ESP-12F") (pin "GPIO4") (pinfunction "4_GPIO4") (pintype "bidirectional"))
      (node (ref "SDA") (pin "1") (pinfunction "1_1") (pintype "passive"))
    )
    (net (code "60") (name "SDA2") (class "Default")
      (node (ref "SDA") (pin "3") (pinfunction "3_3") (pintype "passive"))
      (node (ref "STM32C0") (pin "1") (pinfunction "PB7_1") (pintype "bidirectional"))
    )
    (net (code "61") (name "SWCLK") (class "Default")
      (node (ref "J_DBG2") (pin "4") (pinfunction "SWCLK_4") (pintype "output"))
      (node (ref "J_PRG2") (pin "2") (pinfunction "2_2") (pintype "passive"))
      (node (ref "STM32C0") (pin "19") (pinfunction "PA14-BOOT0_19") (pintype "bidirectional"))
    )
    (net (code "62") (name "SWDIO") (class "Default")
      (node (ref "J_DBG2") (pin "2") (pinfunction "SWDIO_2") (pintype "bidirectional"))
      (node (ref "J_PRG2") (pin "3") (pinfunction "3_3") (pintype "passive"))
      (node (ref "STM32C0") (pin "18") (pinfunction "PA13_18") (pintype "bidirectional"))
    )
    (net (code "63") (name "S_5VIN") (class "Default")
      (node (ref "D1-MINI") (pin "D7") (pinfunction "D7_D7") (pintype "bidirectional"))
      (node (ref "ESP-12F") (pin "GPIO13") (pinfunction "13_GPIO13") (pintype "bidirectional"))
      (node (ref "Q2") (pin "3") (pinfunction "C_3") (pintype "passive"))
      (node (ref "R19") (pin "2") (pinfunction "2_2") (pintype "passive"))
      (node (ref "R5") (pin "1") (pinfunction "1_1") (pintype "passive"))
    )
    (net (code "64") (name "S_HDD_LED") (class "Default")
      (node (ref "D1-MINI") (pin "D5") (pinfunction "D5_D5") (pintype "bidirectional"))
      (node (ref "ESP-12F") (pin "GPIO14") (pinfunction "14_GPIO14") (pintype "bidirectional"))
      (node (ref "Q4") (pin "3") (pinfunction "C_3") (pintype "passive"))
      (node (ref "R11") (pin "1") (pinfunction "1_1") (pintype "passive"))
      (node (ref "R18") (pin "2") (pinfunction "2_2") (pintype "passive"))
    )
    (net (code "65") (name "S_PWR_LED") (class "Default")
      (node (ref "D1-MINI") (pin "D0") (pinfunction "D0_D0") (pintype "bidirectional"))
      (node (ref "Q3") (pin "3") (pinfunction "C_3") (pintype "passive"))
      (node (ref "R12") (pin "1") (pinfunction "1_1") (pintype "passive"))
      (node (ref "R17") (pin "2") (pinfunction "2_2") (pintype "passive"))
    )
    (net (code "66") (name "S_PWR_OK") (class "Default")
      (node (ref "D1-MINI") (pin "D8") (pinfunction "D8_D8") (pintype "bidirectional"))
      (node (ref "ESP-12F") (pin "GPIO15") (pinfunction "15_GPIO15") (pintype "bidirectional"))
      (node (ref "Q1") (pin "3") (pinfunction "C_3") (pintype "passive"))
      (node (ref "R30") (pin "2") (pinfunction "2_2") (pintype "passive"))
      (node (ref "R6") (pin "1") (pinfunction "1_1") (pintype "passive"))
    )
    (net (code "67") (name "TX1") (class "Default")
      (node (ref "D1-MINI") (pin "TX") (pinfunction "TX_TX") (pintype "bidirectional"))
      (node (ref "J_PRG1") (pin "3") (pinfunction "3_3") (pintype "bidirectional"))
      (node (ref "R31") (pin "1") (pinfunction "1_1") (pintype "passive"))
    )
    (net (code "68") (name "TX2") (class "Default")
      (node (ref "STM32C0") (pin "7") (pinfunction "PA0_7") (pintype "bidirectional"))
    )
    (net (code "69") (name "T_PWR_SWT") (class "Default")
      (node (ref "R13") (pin "1") (pinfunction "1_1") (pintype "passive"))
      (node (ref "R25") (pin "2") (pinfunction "2_2") (pintype "passive"))
      (node (ref "STM32C0") (pin "10") (pinfunction "PA3_10") (pintype "bidirectional"))
    )
    (net (code "70") (name "T_RST_SWT") (class "Default")
      (node (ref "R15") (pin "1") (pinfunction "1_1") (pintype "passive"))
      (node (ref "R34") (pin "2") (pinfunction "2_2") (pintype "passive"))
      (node (ref "STM32C0") (pin "9") (pinfunction "PA2_9") (pintype "bidirectional"))
    )
    (net (code "71") (name "VCC") (class "Default")
      (node (ref "C3") (pin "1") (pinfunction "1_1") (pintype "passive"))
      (node (ref "D1-MINI") (pin "5V") (pinfunction "5V_5V") (pintype "power_in"))
      (node (ref "J_I2C") (pin "1") (pinfunction "1_1") (pintype "passive"))
      (node (ref "J_PSU_1") (pin "2") (pinfunction "2_2") (pintype "passive"))
      (node (ref "J_PSU_2") (pin "2") (pinfunction "2_2") (pintype "passive"))
      (node (ref "J_RGB_5V") (pin "3") (pinfunction "3_3") (pintype "passive"))
      (node (ref "TP1") (pin "1") (pinfunction "1_1") (pintype "bidirectional"))
      (node (ref "VREG") (pin "3") (pinfunction "IN_3") (pintype "input"))
    )
    (net (code "72") (name "VDD") (class "Default")
      (node (ref "C1") (pin "1") (pinfunction "1_1") (pintype "passive"))
      (node (ref "C2") (pin "1") (pinfunction "1_1") (pintype "passive"))
      (node (ref "C4") (pin "1") (pinfunction "1_1") (pintype "passive"))
      (node (ref "C8") (pin "1") (pinfunction "1_1") (pintype "passive"))
      (node (ref "C9") (pin "1") (pinfunction "1_1") (pintype "passive"))
      (node (ref "D1-MINI") (pin "3V3") (pinfunction "3V3_3V3") (pintype "power_in"))
      (node (ref "ESP-12F") (pin "VCC") (pinfunction "VCC_VCC") (pintype "bidirectional"))
      (node (ref "I2C") (pin "2") (pinfunction "2_2") (pintype "passive"))
      (node (ref "J_DBG2") (pin "3") (pinfunction "3V3_3") (pintype "power_in"))
      (node (ref "J_I2C") (pin "3") (pinfunction "3_3") (pintype "passive"))
      (node (ref "J_PRG1") (pin "2") (pinfunction "2_2") (pintype "bidirectional"))
      (node (ref "J_PRG2") (pin "4") (pinfunction "4_4") (pintype "passive"))
      (node (ref "J_QWIIC") (pin "2") (pinfunction "2_2") (pintype "power_in"))
      (node (ref "R10") (pin "2") (pinfunction "2_2") (pintype "passive"))
      (node (ref "R11") (pin "2") (pinfunction "2_2") (pintype "passive"))
      (node (ref "R12") (pin "2") (pinfunction "2_2") (pintype "passive"))
      (node (ref "R20") (pin "2") (pinfunction "2_2") (pintype "passive"))
      (node (ref "R27") (pin "2") (pinfunction "2_2") (pintype "passive"))
      (node (ref "R28") (pin "2") (pinfunction "2_2") (pintype "passive"))
      (node (ref "R29") (pin "2") (pinfunction "2_2") (pintype "passive"))
      (node (ref "R3") (pin "2") (pinfunction "2_2") (pintype "passive"))
      (node (ref "R4") (pin "2") (pinfunction "2_2") (pintype "passive"))
      (node (ref "R5") (pin "2") (pinfunction "2_2") (pintype "passive"))
      (node (ref "R6") (pin "2") (pinfunction "2_2") (pintype "passive"))
      (node (ref "R9") (pin "2") (pinfunction "2_2") (pintype "passive"))
      (node (ref "STM32C0") (pin "4") (pinfunction "VDD/VDDA_4") (pintype "power_in"))
      (node (ref "TP2") (pin "1") (pinfunction "1_1") (pintype "bidirectional"))
      (node (ref "VREG") (pin "2") (pinfunction "OUT_2") (pintype "output"))
      (node (ref "VREG") (pin "T") (pinfunction "OUT_T") (pintype "output"))
    )
    (net (code "73") (name "WAKE") (class "Default")
      (node (ref "STM32C0") (pin "11") (pinfunction "PA4_11") (pintype "bidirectional"))
      (node (ref "TP4") (pin "1") (pinfunction "1_1") (pintype "bidirectional"))
    )
    (net (code "74") (name "X_SPARE") (class "Default")
      (node (ref "ARGB") (pin "3") (pinfunction "3_3") (pintype "passive"))
      (node (ref "STM32C0") (pin "15") (pinfunction "PA8_15") (pintype "bidirectional"))
    )
    (net (code "75") (name "~{X_PWR_LONG}") (class "Default")
      (node (ref "D1-MINI") (pin "D3") (pinfunction "D3_D3") (pintype "bidirectional"))
      (node (ref "R33") (pin "1") (pinfunction "1_1") (pintype "passive"))
      (node (ref "STM32C0") (pin "12") (pinfunction "PA5_12") (pintype "bidirectional"))
    )
    (net (code "76") (name "~{X_PWR_SHRT}") (class "Default")
      (node (ref "D1-MINI") (pin "D4") (pinfunction "D4_D4") (pintype "bidirectional"))
      (node (ref "ESP-12F") (pin "GPIO2") (pinfunction "2_GPIO2") (pintype "bidirectional"))
      (node (ref "R28") (pin "1") (pinfunction "1_1") (pintype "passive"))
      (node (ref "STM32C0") (pin "13") (pinfunction "PA6_13") (pintype "bidirectional"))
    )
    (net (code "77") (name "~{X_RST_SHRT}") (class "Default")
      (node (ref "D1-MINI") (pin "D6") (pinfunction "D6_D6") (pintype "bidirectional"))
      (node (ref "ESP-12F") (pin "GPIO12") (pinfunction "12_GPIO12") (pintype "bidirectional"))
      (node (ref "R20") (pin "1") (pinfunction "1_1") (pintype "passive"))
      (node (ref "STM32C0") (pin "14") (pinfunction "PA7_14") (pintype "bidirectional"))
    )
  )
)
